# INTERFACE.net
KiCad netlist of a schematic drawn in Altium Designer
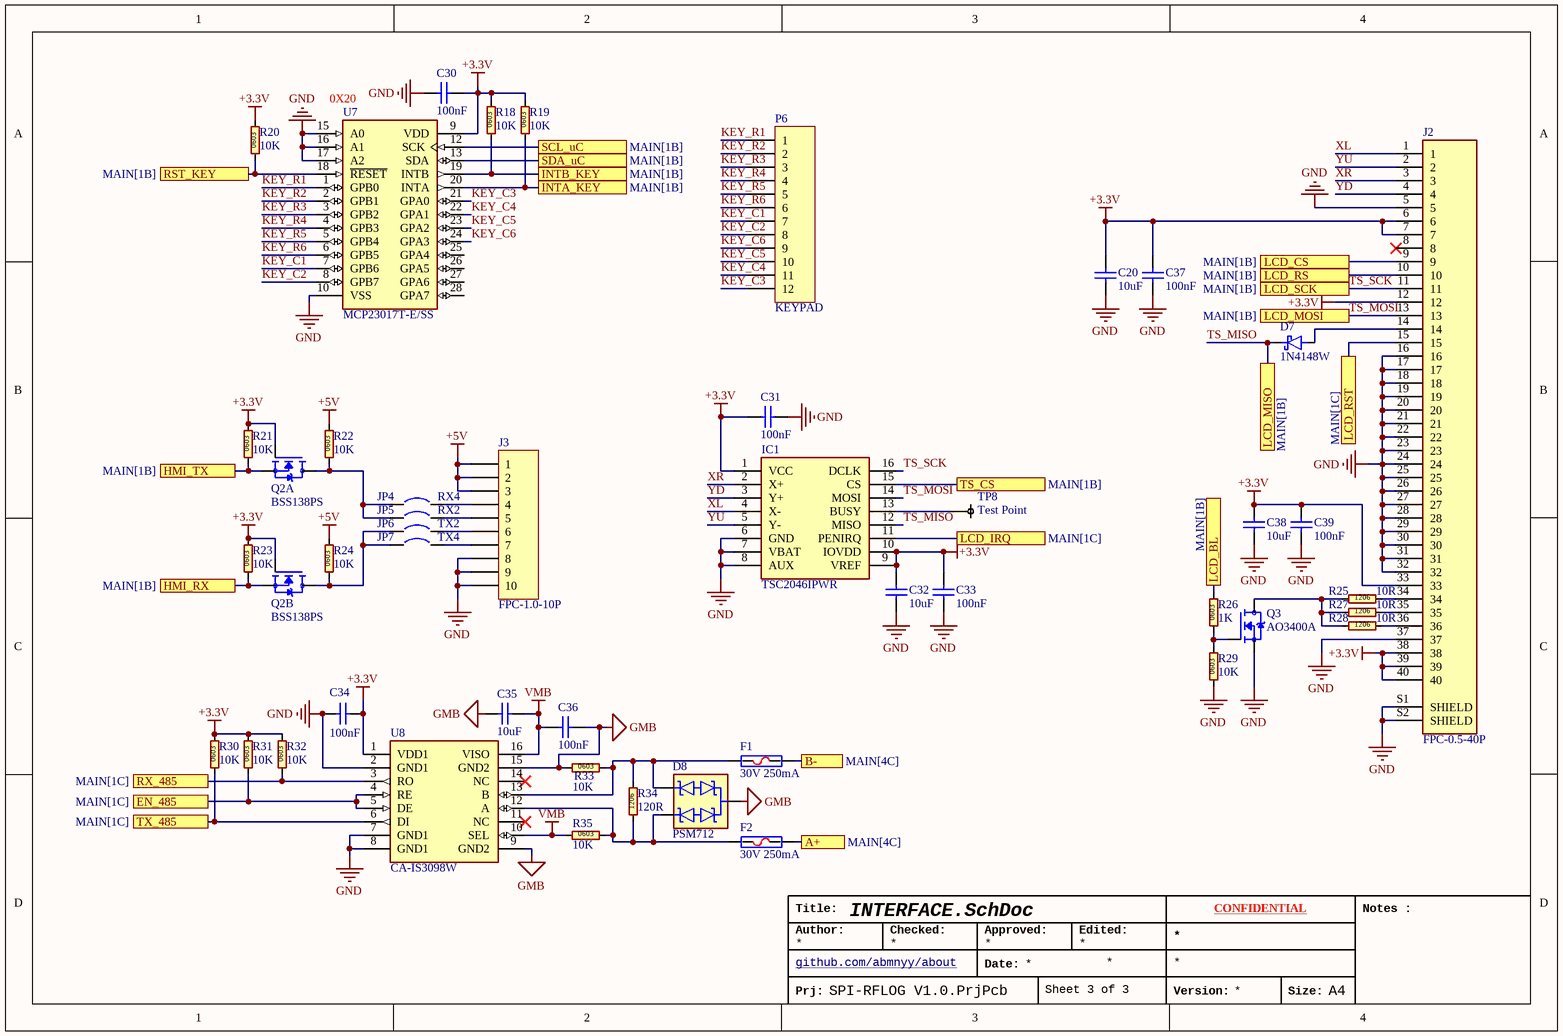
[diagram p0: INTERFACE.SchDoc]

(export (version "E")
  (design (tool "Eeschema 10.0.6"))
  (components
    (comp (ref "C20")
      (value "10uF")
      (footprint "C0603")
      (description "0603 SMD Non-Polarity Capacitor")
      (libsource (lib "AB_SF") (part "Capacitor 0603 (Inch)"))
    )
    (comp (ref "C30")
      (value "100nF")
      (footprint "C0603")
      (description "0603 SMD Non-Polarity Capacitor")
      (libsource (lib "AB_SF") (part "Capacitor 0603 (Inch)"))
    )
    (comp (ref "C31")
      (value "100nF")
      (footprint "C0603")
      (description "0603 SMD Non-Polarity Capacitor")
      (libsource (lib "AB_SF") (part "Capacitor 0603 (Inch)"))
    )
    (comp (ref "C32")
      (value "10uF")
      (footprint "C0603")
      (description "0603 SMD Non-Polarity Capacitor")
      (libsource (lib "AB_SF") (part "Capacitor 0603 (Inch)"))
    )
    (comp (ref "C33")
      (value "100nF")
      (footprint "C0603")
      (description "0603 SMD Non-Polarity Capacitor")
      (libsource (lib "AB_SF") (part "Capacitor 0603 (Inch)"))
    )
    (comp (ref "C34")
      (value "100nF")
      (footprint "C0603")
      (description "0603 SMD Non-Polarity Capacitor")
      (libsource (lib "AB_SF") (part "Capacitor 0603 (Inch)"))
    )
    (comp (ref "C35")
      (value "10uF")
      (footprint "C0603")
      (description "0603 SMD Non-Polarity Capacitor")
      (libsource (lib "AB_SF") (part "Capacitor 0603 (Inch)"))
    )
    (comp (ref "C36")
      (value "100nF")
      (footprint "C0603")
      (description "0603 SMD Non-Polarity Capacitor")
      (libsource (lib "AB_SF") (part "Capacitor 0603 (Inch)"))
    )
    (comp (ref "C37")
      (value "100nF")
      (footprint "C0603")
      (description "0603 SMD Non-Polarity Capacitor")
      (libsource (lib "AB_SF") (part "Capacitor 0603 (Inch)"))
    )
    (comp (ref "C38")
      (value "10uF")
      (footprint "C0603")
      (description "0603 SMD Non-Polarity Capacitor")
      (libsource (lib "AB_SF") (part "Capacitor 0603 (Inch)"))
    )
    (comp (ref "C39")
      (value "100nF")
      (footprint "C0603")
      (description "0603 SMD Non-Polarity Capacitor")
      (libsource (lib "AB_SF") (part "Capacitor 0603 (Inch)"))
    )
    (comp (ref "D7")
      (value "1N4148W")
      (footprint "SOD-123F")
      (description "75V Independent 1V@50mA 4ns 150mA SOD-123 Switching Diodes ROHS")
      (fields (field (name "LCSC PART #") "C81598"))
      (libsource (lib "AI_LIB") (part "1N4148W"))
    )
    (comp (ref "D8")
      (value "PSM712")
      (footprint "SOT-23-3")
      (description "31V, 19V Clamp 19A (8/20µs) Ipp Tvs Diode")
      (fields (field (name "MFR.PART #") "PSM712-LF-T7") (field (name "LCSC PART #") "C2687124"))
      (libsource (lib "AB_SF") (part "PSM712"))
    )
    (comp (ref "F1")
      (value "30V 250mA")
      (footprint "PPTC-1206")
      (description "PPTC RESET FUSE")
      (fields (field (name "MFR.PART #") "BSMD1206-010-30V") (field (name "LCSC PART #") "C5373977"))
      (libsource (lib "AB_SF") (part "PPTC 1206"))
    )
    (comp (ref "F2")
      (value "30V 250mA")
      (footprint "PPTC-1206")
      (description "PPTC RESET FUSE")
      (fields (field (name "MFR.PART #") "BSMD1206-010-30V") (field (name "LCSC PART #") "C5373977"))
      (libsource (lib "AB_SF") (part "PPTC 1206"))
    )
    (comp (ref "IC1")
      (value "TSC2046IPWR")
      (footprint "TSSOP-16")
      (description "12 2V~5.25V TSSOP-16 Touch Screen Controllers ROHS")
      (fields (field (name "LCSC PART #") "C8954"))
      (libsource (lib "AB_SF") (part "TSC2046IPWR"))
    )
    (comp (ref "J2")
      (value "FPC-0.5-40P")
      (footprint "FPC_0.5_40P - TOP CONTACT - duplicate")
      (description "Connector: FFC / FPC; horizontal; PIN: 40; ZIF, top contacts; SMT")
      (fields (field (name "MFR.PART #") "AFC07-S40ECA-00") (field (name "LCSC PART #") "C262648"))
      (libsource (lib "AB_SF") (part "FPC-0.5-40P"))
    )
    (comp (ref "J3")
      (value "FPC-1.0-10P")
      (footprint "FPC_1.0_10P - BOTTOM CONTACT")
      (description "Connector: FFC / FPC; horizontal; PIN: 10; ZIF")
      (fields (field (name "MFR.PART #") "BX-FPC1.0-2H10PX") (field (name "LCSC PART #") "C18077668"))
      (libsource (lib "AB_SF") (part "FPC-1.0-10P"))
    )
    (comp (ref "JP4")
      (value "RX4")
      (footprint "SB_STM")
      (description "Jumper Solder Pad")
      (fields (field (name "PUBLISHER") "Altium Limited"))
      (libsource (lib "AB_SF") (part "Jumper Solder"))
    )
    (comp (ref "JP5")
      (value "RX2")
      (footprint "SB_STM")
      (description "Jumper Solder Pad")
      (fields (field (name "PUBLISHER") "Altium Limited"))
      (libsource (lib "AB_SF") (part "Jumper Solder"))
    )
    (comp (ref "JP6")
      (value "TX2")
      (footprint "SB_STM")
      (description "Jumper Solder Pad")
      (fields (field (name "PUBLISHER") "Altium Limited"))
      (libsource (lib "AB_SF") (part "Jumper Solder"))
    )
    (comp (ref "JP7")
      (value "TX4")
      (footprint "SB_STM")
      (description "Jumper Solder Pad")
      (fields (field (name "PUBLISHER") "Altium Limited"))
      (libsource (lib "AB_SF") (part "Jumper Solder"))
    )
    (comp (ref "P6")
      (value "KEYPAD")
      (footprint "HDR-12P-2.54mm")
      (description "Header, 12-Pin")
      (fields (field (name "PUBLISHER") "Altium Limited"))
      (libsource (lib "AB_SF") (part "Header 12"))
    )
    (comp (ref "Q2")
      (value "BSS138PS")
      (footprint "SOT-363")
      (description "60 V, 320 mA dual N-channel Trench MOSFET")
      (fields (field (name "MFR.PART #") "BSS138PS,115") (field (name "LCSC PART #") "C193381"))
      (libsource (lib "") (part "BSS138PS_1"))
    )
    (comp (ref "Q3")
      (value "AO3400A")
      (footprint "SOT-23-3")
      (description "N-Channel 30 V 5.8A 1.4W")
      (fields (field (name "LCSC PART #") "C20917"))
      (libsource (lib "AB_SF") (part "AO3400A"))
    )
    (comp (ref "R18")
      (value "10K")
      (footprint "R0603")
      (description "0603 SMD Thick Resistor")
      (libsource (lib "AB_SF") (part "Resistor 0603 (Inch)"))
    )
    (comp (ref "R19")
      (value "10K")
      (footprint "R0603")
      (description "0603 SMD Thick Resistor")
      (libsource (lib "AB_SF") (part "Resistor 0603 (Inch)"))
    )
    (comp (ref "R20")
      (value "10K")
      (footprint "R0603")
      (description "0603 SMD Thick Resistor")
      (libsource (lib "AB_SF") (part "Resistor 0603 (Inch)"))
    )
    (comp (ref "R21")
      (value "10K")
      (footprint "R0603")
      (description "0603 SMD Thick Resistor")
      (libsource (lib "AB_SF") (part "Resistor 0603 (Inch)"))
    )
    (comp (ref "R22")
      (value "10K")
      (footprint "R0603")
      (description "0603 SMD Thick Resistor")
      (libsource (lib "AB_SF") (part "Resistor 0603 (Inch)"))
    )
    (comp (ref "R23")
      (value "10K")
      (footprint "R0603")
      (description "0603 SMD Thick Resistor")
      (libsource (lib "AB_SF") (part "Resistor 0603 (Inch)"))
    )
    (comp (ref "R24")
      (value "10K")
      (footprint "R0603")
      (description "0603 SMD Thick Resistor")
      (libsource (lib "AB_SF") (part "Resistor 0603 (Inch)"))
    )
    (comp (ref "R25")
      (value "10R")
      (footprint "R1206")
      (description "1206 SMD Thick Resistor")
      (fields (field (name "MFR.PART #") "RC1206FR-0710RL") (field (name "LCSC PART #") "C108080"))
      (libsource (lib "AB_SF") (part "Resistor 1206 (Inch)"))
    )
    (comp (ref "R26")
      (value "1K")
      (footprint "R0603")
      (description "0603 SMD Thick Resistor")
      (fields (field (name "MFR.PART #") "RC0603JR-071KL") (field (name "LCSC PART #") "C14676"))
      (libsource (lib "AB_SF") (part "Resistor 0603 (Inch)"))
    )
    (comp (ref "R27")
      (value "10R")
      (footprint "R1206")
      (description "1206 SMD Thick Resistor")
      (fields (field (name "MFR.PART #") "RC1206FR-0710RL") (field (name "LCSC PART #") "C108080"))
      (libsource (lib "AB_SF") (part "Resistor 1206 (Inch)"))
    )
    (comp (ref "R28")
      (value "10R")
      (footprint "R1206")
      (description "1206 SMD Thick Resistor")
      (fields (field (name "MFR.PART #") "RC1206FR-0710RL") (field (name "LCSC PART #") "C108080"))
      (libsource (lib "AB_SF") (part "Resistor 1206 (Inch)"))
    )
    (comp (ref "R29")
      (value "10K")
      (footprint "R0603")
      (description "0603 SMD Thick Resistor")
      (libsource (lib "AB_SF") (part "Resistor 0603 (Inch)"))
    )
    (comp (ref "R30")
      (value "10K")
      (footprint "R0603")
      (description "0603 SMD Thick Resistor")
      (libsource (lib "AB_SF") (part "Resistor 0603 (Inch)"))
    )
    (comp (ref "R31")
      (value "10K")
      (footprint "R0603")
      (description "0603 SMD Thick Resistor")
      (libsource (lib "AB_SF") (part "Resistor 0603 (Inch)"))
    )
    (comp (ref "R32")
      (value "10K")
      (footprint "R0603")
      (description "0603 SMD Thick Resistor")
      (libsource (lib "AB_SF") (part "Resistor 0603 (Inch)"))
    )
    (comp (ref "R33")
      (value "10K")
      (footprint "R0603")
      (description "0603 SMD Thick Resistor")
      (libsource (lib "") (part "Resistor 0603 (Inch)_1"))
    )
    (comp (ref "R34")
      (value "120R")
      (footprint "R1206")
      (description "1206 SMD Thick Resistor")
      (fields (field (name "MFR.PART #") "RC1206FR-07120RL") (field (name "LCSC PART #") "C114928"))
      (libsource (lib "") (part "Resistor 1206 (Inch)_1"))
    )
    (comp (ref "R35")
      (value "10K")
      (footprint "R0603")
      (description "0603 SMD Thick Resistor")
      (libsource (lib "") (part "Resistor 0603 (Inch)_1"))
    )
    (comp (ref "TP8")
      (value "Test Point")
      (footprint "PAD")
      (description "Thick Pad")
      (libsource (lib "AB_SF") (part "Test Point"))
    )
    (comp (ref "U7")
      (value "MCP23017T-E/SS")
      (footprint "SSOP-28")
      (fields (field (name "LCSC PART #") "C558584"))
      (libsource (lib "AB_SF") (part "MCP23017T-E/SS"))
    )
    (comp (ref "U8")
      (value "CA-IS3098W")
      (footprint "SOIC-16-WIDE")
      (description "SOIC16-WB(W) Isolated RS-485/422 Transceivers with power, 20Mbps")
      (fields (field (name "LCSC PART #") "C7422557"))
      (libsource (lib "AB_SF") (part "CA-IS3098W"))
    )
  )
  (nets
    (net (code "1") (name "+3.3V") (class "Default")
      (node (ref "C20") (pin "1") (pinfunction "1_1") (pintype "passive"))
      (node (ref "C30") (pin "2") (pinfunction "2_2") (pintype "passive"))
      (node (ref "C31") (pin "2") (pinfunction "2_2") (pintype "passive"))
      (node (ref "C32") (pin "1") (pinfunction "1_1") (pintype "passive"))
      (node (ref "C33") (pin "2") (pinfunction "2_2") (pintype "passive"))
      (node (ref "C34") (pin "2") (pinfunction "2_2") (pintype "passive"))
      (node (ref "C37") (pin "2") (pinfunction "2_2") (pintype "passive"))
      (node (ref "C38") (pin "1") (pinfunction "1_1") (pintype "passive"))
      (node (ref "C39") (pin "2") (pinfunction "2_2") (pintype "passive"))
      (node (ref "IC1") (pin "1") (pinfunction "VCC_1") (pintype "passive"))
      (node (ref "IC1") (pin "10") (pinfunction "IOVDD_10") (pintype "passive"))
      (node (ref "IC1") (pin "9") (pinfunction "VREF_9") (pintype "passive"))
      (node (ref "J2") (pin "12") (pinfunction "12_12") (pintype "passive"))
      (node (ref "J2") (pin "33") (pinfunction "33_33") (pintype "passive"))
      (node (ref "J2") (pin "38") (pinfunction "38_38") (pintype "passive"))
      (node (ref "J2") (pin "39") (pinfunction "39_39") (pintype "passive"))
      (node (ref "J2") (pin "40") (pinfunction "40_40") (pintype "passive"))
      (node (ref "J2") (pin "6") (pinfunction "6_6") (pintype "passive"))
      (node (ref "J2") (pin "7") (pinfunction "7_7") (pintype "passive"))
      (node (ref "Q2") (pin "2") (pinfunction "G1_2") (pintype "passive"))
      (node (ref "Q2") (pin "5") (pinfunction "G2_5") (pintype "passive"))
      (node (ref "R18") (pin "2") (pinfunction "2_2") (pintype "passive"))
      (node (ref "R19") (pin "2") (pinfunction "2_2") (pintype "passive"))
      (node (ref "R20") (pin "2") (pinfunction "2_2") (pintype "passive"))
      (node (ref "R21") (pin "2") (pinfunction "2_2") (pintype "passive"))
      (node (ref "R23") (pin "2") (pinfunction "2_2") (pintype "passive"))
      (node (ref "R30") (pin "2") (pinfunction "2_2") (pintype "passive"))
      (node (ref "R31") (pin "2") (pinfunction "2_2") (pintype "passive"))
      (node (ref "R32") (pin "2") (pinfunction "2_2") (pintype "passive"))
      (node (ref "U7") (pin "9") (pinfunction "VDD_9") (pintype "power_in"))
      (node (ref "U8") (pin "1") (pinfunction "VDD1_1") (pintype "power_in"))
    )
    (net (code "2") (name "+5V") (class "Default")
      (node (ref "J3") (pin "1") (pinfunction "1_1") (pintype "passive"))
      (node (ref "J3") (pin "2") (pinfunction "2_2") (pintype "passive"))
      (node (ref "J3") (pin "3") (pinfunction "3_3") (pintype "passive"))
      (node (ref "R22") (pin "2") (pinfunction "2_2") (pintype "passive"))
      (node (ref "R24") (pin "2") (pinfunction "2_2") (pintype "passive"))
    )
    (net (code "3") (name "/A+") (class "Default")
      (node (ref "F2") (pin "2") (pinfunction "2_2") (pintype "passive"))
    )
    (net (code "4") (name "/B-") (class "Default")
      (node (ref "F1") (pin "2") (pinfunction "2_2") (pintype "passive"))
    )
    (net (code "5") (name "/EN_485") (class "Default")
      (node (ref "R31") (pin "1") (pinfunction "1_1") (pintype "passive"))
      (node (ref "U8") (pin "4") (pinfunction "RE_4") (pintype "input"))
      (node (ref "U8") (pin "5") (pinfunction "DE_5") (pintype "input"))
    )
    (net (code "6") (name "/HMI_RX") (class "Default")
      (node (ref "Q2") (pin "4") (pinfunction "S2_4") (pintype "passive"))
      (node (ref "R23") (pin "1") (pinfunction "1_1") (pintype "passive"))
    )
    (net (code "7") (name "/HMI_TX") (class "Default")
      (node (ref "Q2") (pin "1") (pinfunction "S1_1") (pintype "passive"))
      (node (ref "R21") (pin "1") (pinfunction "1_1") (pintype "passive"))
    )
    (net (code "8") (name "/INTA_KEY") (class "Default")
      (node (ref "R19") (pin "1") (pinfunction "1_1") (pintype "passive"))
      (node (ref "U7") (pin "20") (pinfunction "INTA_20") (pintype "output"))
    )
    (net (code "9") (name "/INTB_KEY") (class "Default")
      (node (ref "R18") (pin "1") (pinfunction "1_1") (pintype "passive"))
      (node (ref "U7") (pin "19") (pinfunction "INTB_19") (pintype "output"))
    )
    (net (code "10") (name "/KEY_C1") (class "Default")
      (node (ref "P6") (pin "7") (pinfunction "7_7") (pintype "passive"))
      (node (ref "U7") (pin "7") (pinfunction "GPB6_7") (pintype "bidirectional"))
    )
    (net (code "11") (name "/KEY_C2") (class "Default")
      (node (ref "P6") (pin "8") (pinfunction "8_8") (pintype "passive"))
      (node (ref "U7") (pin "8") (pinfunction "GPB7_8") (pintype "bidirectional"))
    )
    (net (code "12") (name "/KEY_C3") (class "Default")
      (node (ref "P6") (pin "12") (pinfunction "12_12") (pintype "passive"))
      (node (ref "U7") (pin "21") (pinfunction "GPA0_21") (pintype "bidirectional"))
    )
    (net (code "13") (name "/KEY_C4") (class "Default")
      (node (ref "P6") (pin "11") (pinfunction "11_11") (pintype "passive"))
      (node (ref "U7") (pin "22") (pinfunction "GPA1_22") (pintype "bidirectional"))
    )
    (net (code "14") (name "/KEY_C5") (class "Default")
      (node (ref "P6") (pin "10") (pinfunction "10_10") (pintype "passive"))
      (node (ref "U7") (pin "23") (pinfunction "GPA2_23") (pintype "bidirectional"))
    )
    (net (code "15") (name "/KEY_C6") (class "Default")
      (node (ref "P6") (pin "9") (pinfunction "9_9") (pintype "passive"))
      (node (ref "U7") (pin "24") (pinfunction "GPA3_24") (pintype "bidirectional"))
    )
    (net (code "16") (name "/KEY_R1") (class "Default")
      (node (ref "P6") (pin "1") (pinfunction "1_1") (pintype "passive"))
      (node (ref "U7") (pin "1") (pinfunction "GPB0_1") (pintype "bidirectional"))
    )
    (net (code "17") (name "/KEY_R2") (class "Default")
      (node (ref "P6") (pin "2") (pinfunction "2_2") (pintype "passive"))
      (node (ref "U7") (pin "2") (pinfunction "GPB1_2") (pintype "bidirectional"))
    )
    (net (code "18") (name "/KEY_R3") (class "Default")
      (node (ref "P6") (pin "3") (pinfunction "3_3") (pintype "passive"))
      (node (ref "U7") (pin "3") (pinfunction "GPB2_3") (pintype "bidirectional"))
    )
    (net (code "19") (name "/KEY_R4") (class "Default")
      (node (ref "P6") (pin "4") (pinfunction "4_4") (pintype "passive"))
      (node (ref "U7") (pin "4") (pinfunction "GPB3_4") (pintype "bidirectional"))
    )
    (net (code "20") (name "/KEY_R5") (class "Default")
      (node (ref "P6") (pin "5") (pinfunction "5_5") (pintype "passive"))
      (node (ref "U7") (pin "5") (pinfunction "GPB4_5") (pintype "bidirectional"))
    )
    (net (code "21") (name "/KEY_R6") (class "Default")
      (node (ref "P6") (pin "6") (pinfunction "6_6") (pintype "passive"))
      (node (ref "U7") (pin "6") (pinfunction "GPB5_6") (pintype "bidirectional"))
    )
    (net (code "22") (name "/LCD_BL") (class "Default")
      (node (ref "R26") (pin "2") (pinfunction "2_2") (pintype "passive"))
    )
    (net (code "23") (name "/LCD_CS") (class "Default")
      (node (ref "J2") (pin "9") (pinfunction "9_9") (pintype "passive"))
    )
    (net (code "24") (name "/LCD_IRQ") (class "Default")
      (node (ref "IC1") (pin "11") (pinfunction "PENIRQ_11") (pintype "passive"))
    )
    (net (code "25") (name "/LCD_RS") (class "Default")
      (node (ref "J2") (pin "10") (pinfunction "10_10") (pintype "passive"))
    )
    (net (code "26") (name "/LCD_RST") (class "Default")
      (node (ref "J2") (pin "15") (pinfunction "15_15") (pintype "passive"))
    )
    (net (code "27") (name "/RST_KEY") (class "Default")
      (node (ref "R20") (pin "1") (pinfunction "1_1") (pintype "passive"))
      (node (ref "U7") (pin "18") (pinfunction "~{RESET}_18") (pintype "input"))
    )
    (net (code "28") (name "/RX_485") (class "Default")
      (node (ref "R32") (pin "1") (pinfunction "1_1") (pintype "passive"))
      (node (ref "U8") (pin "3") (pinfunction "RO_3") (pintype "output"))
    )
    (net (code "29") (name "/SCL_uC") (class "Default")
      (node (ref "U7") (pin "12") (pinfunction "SCK_12") (pintype "input"))
    )
    (net (code "30") (name "/SDA_uC") (class "Default")
      (node (ref "U7") (pin "13") (pinfunction "SDA_13") (pintype "bidirectional"))
    )
    (net (code "31") (name "/TS_CS") (class "Default")
      (node (ref "IC1") (pin "15") (pinfunction "CS_15") (pintype "passive"))
    )
    (net (code "32") (name "/TS_MISO") (class "Default")
      (node (ref "D7") (pin "K") (pinfunction "K_K") (pintype "passive"))
      (node (ref "IC1") (pin "12") (pinfunction "MISO_12") (pintype "passive"))
    )
    (net (code "33") (name "/TS_MOSI") (class "Default")
      (node (ref "IC1") (pin "14") (pinfunction "MOSI_14") (pintype "passive"))
      (node (ref "J2") (pin "13") (pinfunction "13_13") (pintype "passive"))
    )
    (net (code "34") (name "/TS_SCK") (class "Default")
      (node (ref "IC1") (pin "16") (pinfunction "DCLK_16") (pintype "passive"))
      (node (ref "J2") (pin "11") (pinfunction "11_11") (pintype "passive"))
    )
    (net (code "35") (name "/TX_485") (class "Default")
      (node (ref "R30") (pin "1") (pinfunction "1_1") (pintype "passive"))
      (node (ref "U8") (pin "6") (pinfunction "DI_6") (pintype "output"))
    )
    (net (code "36") (name "/XL") (class "Default")
      (node (ref "IC1") (pin "4") (pinfunction "X-_4") (pintype "passive"))
      (node (ref "J2") (pin "1") (pinfunction "1_1") (pintype "passive"))
    )
    (net (code "37") (name "/XR") (class "Default")
      (node (ref "IC1") (pin "2") (pinfunction "X+_2") (pintype "passive"))
      (node (ref "J2") (pin "3") (pinfunction "3_3") (pintype "passive"))
    )
    (net (code "38") (name "/YD") (class "Default")
      (node (ref "IC1") (pin "3") (pinfunction "Y+_3") (pintype "passive"))
      (node (ref "J2") (pin "4") (pinfunction "4_4") (pintype "passive"))
    )
    (net (code "39") (name "/YU") (class "Default")
      (node (ref "IC1") (pin "5") (pinfunction "Y-_5") (pintype "passive"))
      (node (ref "J2") (pin "2") (pinfunction "2_2") (pintype "passive"))
    )
    (net (code "40") (name "GMB") (class "Default")
      (node (ref "C35") (pin "2") (pinfunction "2_2") (pintype "passive"))
      (node (ref "C36") (pin "2") (pinfunction "2_2") (pintype "passive"))
      (node (ref "D8") (pin "3") (pinfunction "3_3") (pintype "passive"))
      (node (ref "R33") (pin "1") (pinfunction "1_1") (pintype "passive"))
      (node (ref "U8") (pin "15") (pinfunction "GND2_15") (pintype "power_in"))
      (node (ref "U8") (pin "9") (pinfunction "GND2_9") (pintype "power_in"))
    )
    (net (code "41") (name "GND") (class "Default")
      (node (ref "C20") (pin "2") (pinfunction "2_2") (pintype "passive"))
      (node (ref "C30") (pin "1") (pinfunction "1_1") (pintype "passive"))
      (node (ref "C31") (pin "1") (pinfunction "1_1") (pintype "passive"))
      (node (ref "C32") (pin "2") (pinfunction "2_2") (pintype "passive"))
      (node (ref "C33") (pin "1") (pinfunction "1_1") (pintype "passive"))
      (node (ref "C34") (pin "1") (pinfunction "1_1") (pintype "passive"))
      (node (ref "C37") (pin "1") (pinfunction "1_1") (pintype "passive"))
      (node (ref "C38") (pin "2") (pinfunction "2_2") (pintype "passive"))
      (node (ref "C39") (pin "1") (pinfunction "1_1") (pintype "passive"))
      (node (ref "IC1") (pin "6") (pinfunction "GND_6") (pintype "passive"))
      (node (ref "IC1") (pin "7") (pinfunction "VBAT_7") (pintype "passive"))
      (node (ref "IC1") (pin "8") (pinfunction "AUX_8") (pintype "passive"))
      (node (ref "J2") (pin "16") (pinfunction "16_16") (pintype "passive"))
      (node (ref "J2") (pin "17") (pinfunction "17_17") (pintype "passive"))
      (node (ref "J2") (pin "18") (pinfunction "18_18") (pintype "passive"))
      (node (ref "J2") (pin "19") (pinfunction "19_19") (pintype "passive"))
      (node (ref "J2") (pin "20") (pinfunction "20_20") (pintype "passive"))
      (node (ref "J2") (pin "21") (pinfunction "21_21") (pintype "passive"))
      (node (ref "J2") (pin "22") (pinfunction "22_22") (pintype "passive"))
      (node (ref "J2") (pin "23") (pinfunction "23_23") (pintype "passive"))
      (node (ref "J2") (pin "24") (pinfunction "24_24") (pintype "passive"))
      (node (ref "J2") (pin "25") (pinfunction "25_25") (pintype "passive"))
      (node (ref "J2") (pin "26") (pinfunction "26_26") (pintype "passive"))
      (node (ref "J2") (pin "27") (pinfunction "27_27") (pintype "passive"))
      (node (ref "J2") (pin "28") (pinfunction "28_28") (pintype "passive"))
      (node (ref "J2") (pin "29") (pinfunction "29_29") (pintype "passive"))
      (node (ref "J2") (pin "30") (pinfunction "30_30") (pintype "passive"))
      (node (ref "J2") (pin "31") (pinfunction "31_31") (pintype "passive"))
      (node (ref "J2") (pin "32") (pinfunction "32_32") (pintype "passive"))
      (node (ref "J2") (pin "37") (pinfunction "37_37") (pintype "passive"))
      (node (ref "J2") (pin "5") (pinfunction "5_5") (pintype "passive"))
      (node (ref "J2") (pin "S1") (pinfunction "SHIELD_S1") (pintype "passive"))
      (node (ref "J2") (pin "S2") (pinfunction "SHIELD_S2") (pintype "passive"))
      (node (ref "J3") (pin "10") (pinfunction "10_10") (pintype "passive"))
      (node (ref "J3") (pin "8") (pinfunction "8_8") (pintype "passive"))
      (node (ref "J3") (pin "9") (pinfunction "9_9") (pintype "passive"))
      (node (ref "Q3") (pin "2") (pinfunction "S_2") (pintype "passive"))
      (node (ref "R29") (pin "1") (pinfunction "1_1") (pintype "passive"))
      (node (ref "U7") (pin "10") (pinfunction "VSS_10") (pintype "power_in"))
      (node (ref "U7") (pin "15") (pinfunction "A0_15") (pintype "input"))
      (node (ref "U7") (pin "16") (pinfunction "A1_16") (pintype "input"))
      (node (ref "U7") (pin "17") (pinfunction "A2_17") (pintype "input"))
      (node (ref "U8") (pin "2") (pinfunction "GND1_2") (pintype "power_in"))
      (node (ref "U8") (pin "7") (pinfunction "GND1_7") (pintype "power_in"))
      (node (ref "U8") (pin "8") (pinfunction "GND1_8") (pintype "power_in"))
    )
    (net (code "42") (name "Net-(D7-PadA)") (class "Default")
      (node (ref "D7") (pin "A") (pinfunction "A_A") (pintype "passive"))
      (node (ref "J2") (pin "14") (pinfunction "14_14") (pintype "passive"))
    )
    (net (code "43") (name "Net-(IC1-BUSY)") (class "Default")
      (node (ref "IC1") (pin "13") (pinfunction "BUSY_13") (pintype "passive"))
      (node (ref "TP8") (pin "1") (pinfunction "1_1") (pintype "passive"))
    )
    (net (code "44") (name "Net-(J2-Pad34)") (class "Default")
      (node (ref "J2") (pin "34") (pinfunction "34_34") (pintype "passive"))
      (node (ref "R25") (pin "2") (pinfunction "2_2") (pintype "passive"))
    )
    (net (code "45") (name "Net-(J2-Pad35)") (class "Default")
      (node (ref "J2") (pin "35") (pinfunction "35_35") (pintype "passive"))
      (node (ref "R27") (pin "2") (pinfunction "2_2") (pintype "passive"))
    )
    (net (code "46") (name "Net-(J2-Pad36)") (class "Default")
      (node (ref "J2") (pin "36") (pinfunction "36_36") (pintype "passive"))
      (node (ref "R28") (pin "2") (pinfunction "2_2") (pintype "passive"))
    )
    (net (code "47") (name "Net-(J3-Pad4)") (class "Default")
      (node (ref "J3") (pin "4") (pinfunction "4_4") (pintype "passive"))
      (node (ref "JP4") (pin "2") (pinfunction "2_2") (pintype "passive"))
    )
    (net (code "48") (name "Net-(J3-Pad5)") (class "Default")
      (node (ref "J3") (pin "5") (pinfunction "5_5") (pintype "passive"))
      (node (ref "JP5") (pin "2") (pinfunction "2_2") (pintype "passive"))
    )
    (net (code "49") (name "Net-(J3-Pad6)") (class "Default")
      (node (ref "J3") (pin "6") (pinfunction "6_6") (pintype "passive"))
      (node (ref "JP6") (pin "2") (pinfunction "2_2") (pintype "passive"))
    )
    (net (code "50") (name "Net-(J3-Pad7)") (class "Default")
      (node (ref "J3") (pin "7") (pinfunction "7_7") (pintype "passive"))
      (node (ref "JP7") (pin "2") (pinfunction "2_2") (pintype "passive"))
    )
    (net (code "51") (name "Net-(Q2A-D1)") (class "Default")
      (node (ref "JP4") (pin "1") (pinfunction "1_1") (pintype "passive"))
      (node (ref "JP5") (pin "1") (pinfunction "1_1") (pintype "passive"))
      (node (ref "Q2") (pin "6") (pinfunction "D1_6") (pintype "passive"))
      (node (ref "R22") (pin "1") (pinfunction "1_1") (pintype "passive"))
    )
    (net (code "52") (name "Net-(Q2B-D2)") (class "Default")
      (node (ref "JP6") (pin "1") (pinfunction "1_1") (pintype "passive"))
      (node (ref "JP7") (pin "1") (pinfunction "1_1") (pintype "passive"))
      (node (ref "Q2") (pin "3") (pinfunction "D2_3") (pintype "passive"))
      (node (ref "R24") (pin "1") (pinfunction "1_1") (pintype "passive"))
    )
    (net (code "53") (name "Net-(Q3-D)") (class "Default")
      (node (ref "Q3") (pin "3") (pinfunction "D_3") (pintype "passive"))
      (node (ref "R25") (pin "1") (pinfunction "1_1") (pintype "passive"))
      (node (ref "R27") (pin "1") (pinfunction "1_1") (pintype "passive"))
      (node (ref "R28") (pin "1") (pinfunction "1_1") (pintype "passive"))
    )
    (net (code "54") (name "Net-(Q3-G)") (class "Default")
      (node (ref "Q3") (pin "1") (pinfunction "G_1") (pintype "passive"))
      (node (ref "R26") (pin "1") (pinfunction "1_1") (pintype "passive"))
      (node (ref "R29") (pin "2") (pinfunction "2_2") (pintype "passive"))
    )
    (net (code "55") (name "Net-(U8-A)") (class "Default")
      (node (ref "D8") (pin "2") (pinfunction "2_2") (pintype "passive"))
      (node (ref "F2") (pin "1") (pinfunction "1_1") (pintype "passive"))
      (node (ref "R34") (pin "1") (pinfunction "1_1") (pintype "passive"))
      (node (ref "R35") (pin "2") (pinfunction "2_2") (pintype "passive"))
      (node (ref "U8") (pin "12") (pinfunction "A_12") (pintype "bidirectional"))
    )
    (net (code "56") (name "Net-(U8-B)") (class "Default")
      (node (ref "D8") (pin "1") (pinfunction "1_1") (pintype "passive"))
      (node (ref "F1") (pin "1") (pinfunction "1_1") (pintype "passive"))
      (node (ref "R33") (pin "2") (pinfunction "2_2") (pintype "passive"))
      (node (ref "R34") (pin "2") (pinfunction "2_2") (pintype "passive"))
      (node (ref "U8") (pin "13") (pinfunction "B_13") (pintype "bidirectional"))
    )
    (net (code "57") (name "VMB") (class "Default")
      (node (ref "C35") (pin "1") (pinfunction "1_1") (pintype "passive"))
      (node (ref "C36") (pin "1") (pinfunction "1_1") (pintype "passive"))
      (node (ref "R35") (pin "1") (pinfunction "1_1") (pintype "passive"))
      (node (ref "U8") (pin "10") (pinfunction "SEL_10") (pintype "bidirectional"))
      (node (ref "U8") (pin "16") (pinfunction "VISO_16") (pintype "power_in"))
    )
    (net (code "58") (name "unconnected-(J2-Pad8)") (class "Default")
      (node (ref "J2") (pin "8") (pinfunction "8_8") (pintype "passive+no_connect"))
    )
    (net (code "59") (name "unconnected-(U7-GPA4-Pad25)") (class "Default")
      (node (ref "U7") (pin "25") (pinfunction "GPA4_25") (pintype "bidirectional"))
    )
    (net (code "60") (name "unconnected-(U7-GPA5-Pad26)") (class "Default")
      (node (ref "U7") (pin "26") (pinfunction "GPA5_26") (pintype "bidirectional"))
    )
    (net (code "61") (name "unconnected-(U7-GPA6-Pad27)") (class "Default")
      (node (ref "U7") (pin "27") (pinfunction "GPA6_27") (pintype "bidirectional"))
    )
    (net (code "62") (name "unconnected-(U7-GPA7-Pad28)") (class "Default")
      (node (ref "U7") (pin "28") (pinfunction "GPA7_28") (pintype "bidirectional"))
    )
    (net (code "63") (name "unconnected-(U8-NC-Pad11)") (class "Default")
      (node (ref "U8") (pin "11") (pinfunction "NC_11") (pintype "passive+no_connect"))
    )
    (net (code "64") (name "unconnected-(U8-NC-Pad14)") (class "Default")
      (node (ref "U8") (pin "14") (pinfunction "NC_14") (pintype "passive+no_connect"))
    )
  )
)
